# AIO.net
KiCad netlist of a schematic drawn in EAGLE
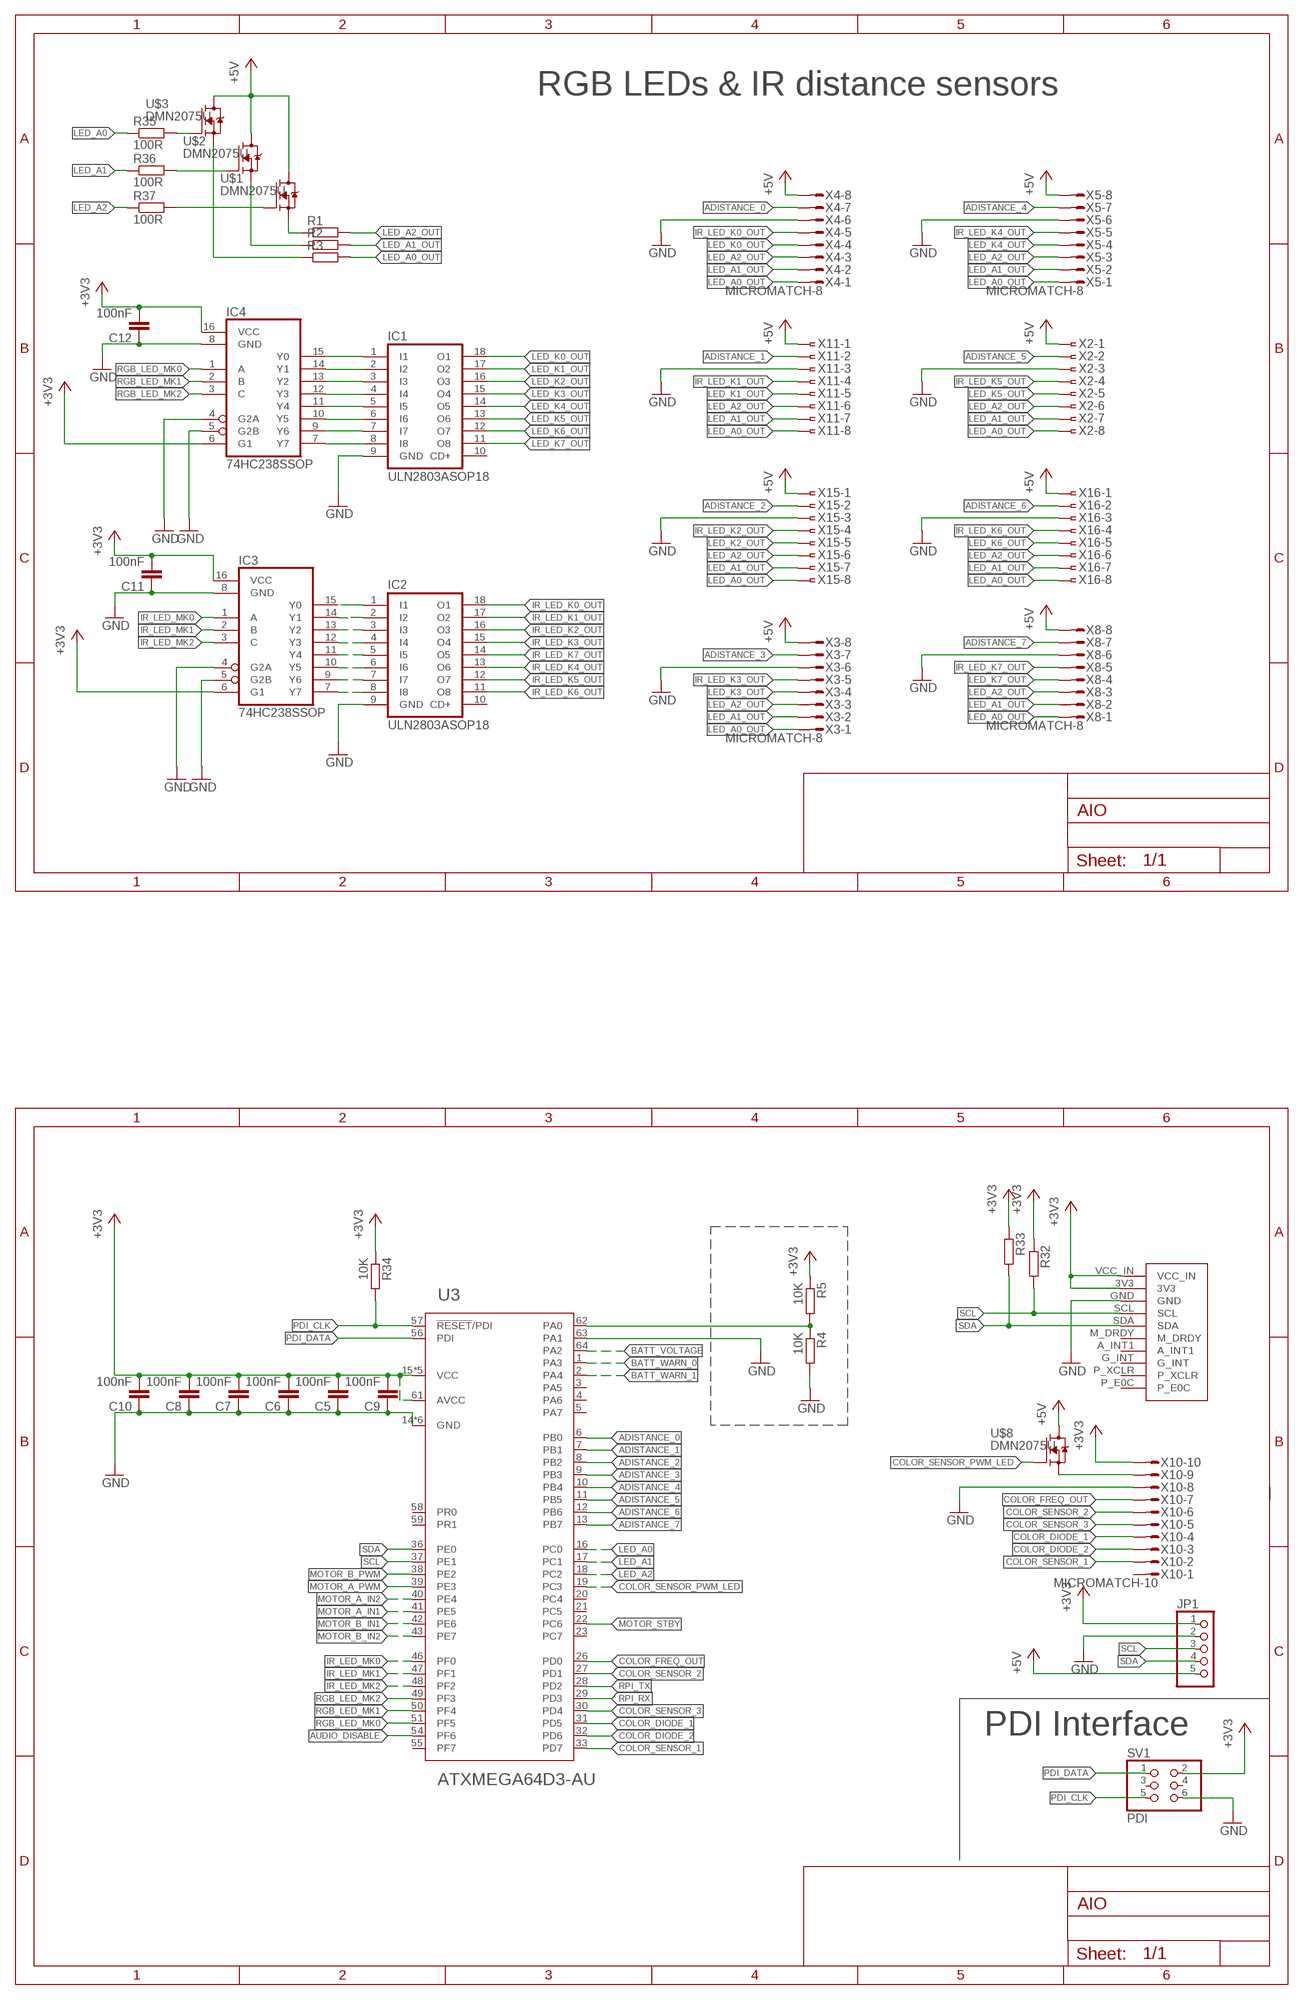
[diagram p0: schematic, sheet 1, part 1 of 2]
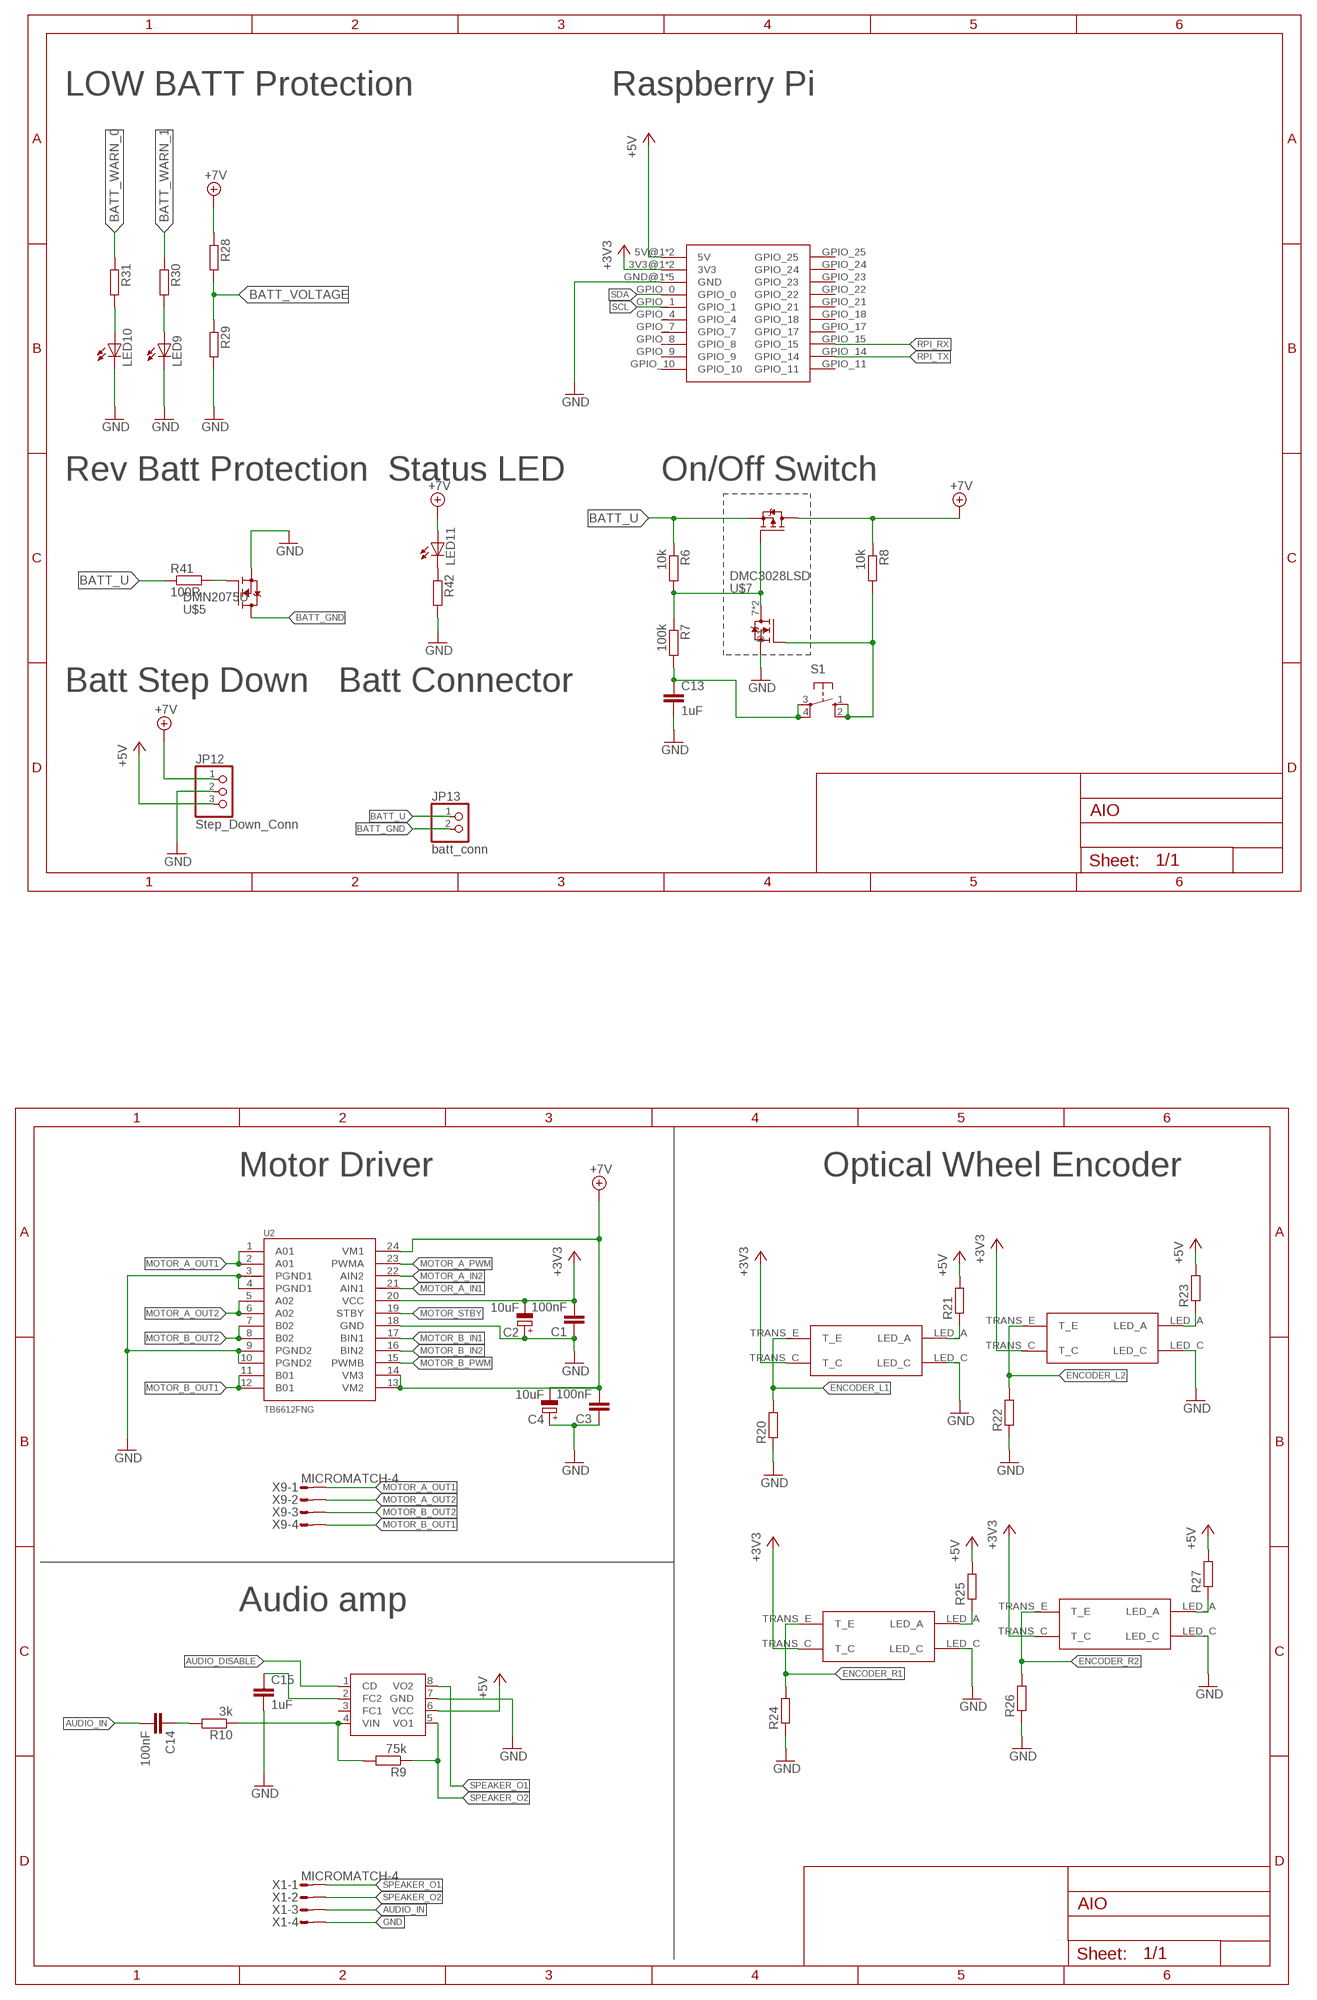
[diagram p1: schematic, sheet 1, part 2 of 2]

(export (version "E")
  (design (tool "Eeschema 10.0.6"))
  (components
    (comp (ref "C1")
      (value "100nF")
      (footprint "eagle-import:C0603")
      (libsource (lib "eagle-import") (part "C-EUC0603"))
    )
    (comp (ref "C2")
      (value "10uF")
      (footprint "eagle-import:SMC_D")
      (libsource (lib "eagle-import") (part "CPOL-EUSMCD"))
    )
    (comp (ref "C3")
      (value "100nF")
      (footprint "eagle-import:C0603")
      (libsource (lib "eagle-import") (part "C-EUC0603"))
    )
    (comp (ref "C4")
      (value "10uF")
      (footprint "eagle-import:SMC_D")
      (libsource (lib "eagle-import") (part "CPOL-EUSMCD"))
    )
    (comp (ref "C5")
      (value "100nF")
      (footprint "eagle-import:C0603")
      (libsource (lib "eagle-import") (part "C-EUC0603"))
    )
    (comp (ref "C6")
      (value "100nF")
      (footprint "eagle-import:C0603")
      (libsource (lib "eagle-import") (part "C-EUC0603"))
    )
    (comp (ref "C7")
      (value "100nF")
      (footprint "eagle-import:C0603")
      (libsource (lib "eagle-import") (part "C-EUC0603"))
    )
    (comp (ref "C8")
      (value "100nF")
      (footprint "eagle-import:C0603")
      (libsource (lib "eagle-import") (part "C-EUC0603"))
    )
    (comp (ref "C9")
      (value "100nF")
      (footprint "eagle-import:C0603")
      (libsource (lib "eagle-import") (part "C-EUC0603"))
    )
    (comp (ref "C10")
      (value "100nF")
      (footprint "eagle-import:C0603")
      (libsource (lib "eagle-import") (part "C-EUC0603"))
    )
    (comp (ref "C11")
      (value "100nF")
      (footprint "eagle-import:C0603")
      (libsource (lib "eagle-import") (part "C-EUC0603"))
    )
    (comp (ref "C12")
      (value "100nF")
      (footprint "eagle-import:C0603")
      (libsource (lib "eagle-import") (part "C-EUC0603"))
    )
    (comp (ref "C13")
      (value "1uF")
      (footprint "eagle-import:C0603")
      (libsource (lib "eagle-import") (part "C-EUC0603"))
    )
    (comp (ref "C14")
      (value "100nF")
      (footprint "eagle-import:C0603")
      (libsource (lib "eagle-import") (part "C-EUC0603"))
    )
    (comp (ref "C15")
      (value "1uF")
      (footprint "eagle-import:C0603")
      (libsource (lib "eagle-import") (part "C-EUC0603"))
    )
    (comp (ref "IC1")
      (value "ULN2803ASOP18")
      (footprint "eagle-import:SOP18")
      (libsource (lib "eagle-import") (part "ULN2803ASOP18"))
    )
    (comp (ref "IC2")
      (value "ULN2803ASOP18")
      (footprint "eagle-import:SOP18")
      (libsource (lib "eagle-import") (part "ULN2803ASOP18"))
    )
    (comp (ref "IC3")
      (value "74HC238SSOP")
      (footprint "eagle-import:SSOP16")
      (libsource (lib "eagle-import") (part "74HC238SSOP"))
    )
    (comp (ref "IC4")
      (value "74HC238SSOP")
      (footprint "eagle-import:SSOP16")
      (libsource (lib "eagle-import") (part "74HC238SSOP"))
    )
    (comp (ref "IC5")
      (value "TS34119SMD")
      (footprint "eagle-import:SO08")
      (libsource (lib "eagle-import") (part "TS34119SMD"))
    )
    (comp (ref "JP1")
      (value "PINHD-1X5")
      (footprint "eagle-import:1X05")
      (libsource (lib "eagle-import") (part "PINHD-1X5"))
    )
    (comp (ref "JP12")
      (value "Step_Down_Conn")
      (footprint "eagle-import:1X03")
      (libsource (lib "eagle-import") (part "PINHD-1X3"))
    )
    (comp (ref "JP13")
      (value "batt_conn")
      (footprint "eagle-import:1X02")
      (libsource (lib "eagle-import") (part "PINHD-1X2"))
    )
    (comp (ref "LED9")
      (value "LEDCHIPLED_0603")
      (footprint "eagle-import:CHIPLED_0603")
      (libsource (lib "eagle-import") (part "LEDCHIPLED_0603"))
    )
    (comp (ref "LED10")
      (value "LEDCHIPLED_0603")
      (footprint "eagle-import:CHIPLED_0603")
      (libsource (lib "eagle-import") (part "LEDCHIPLED_0603"))
    )
    (comp (ref "LED11")
      (value "LEDCHIPLED_0603")
      (footprint "eagle-import:CHIPLED_0603")
      (libsource (lib "eagle-import") (part "LEDCHIPLED_0603"))
    )
    (comp (ref "R1")
      (value "R-EU_R0603")
      (footprint "eagle-import:R0603")
      (libsource (lib "eagle-import") (part "R-EU_R0603"))
    )
    (comp (ref "R2")
      (value "R-EU_R0603")
      (footprint "eagle-import:R0603")
      (libsource (lib "eagle-import") (part "R-EU_R0603"))
    )
    (comp (ref "R3")
      (value "R-EU_R0603")
      (footprint "eagle-import:R0603")
      (libsource (lib "eagle-import") (part "R-EU_R0603"))
    )
    (comp (ref "R4")
      (value "10K")
      (footprint "eagle-import:R0603")
      (libsource (lib "eagle-import") (part "R-EU_R0603"))
    )
    (comp (ref "R5")
      (value "10K")
      (footprint "eagle-import:R0603")
      (libsource (lib "eagle-import") (part "R-EU_R0603"))
    )
    (comp (ref "R6")
      (value "10k")
      (footprint "eagle-import:R0603")
      (libsource (lib "eagle-import") (part "R-EU_R0603"))
    )
    (comp (ref "R7")
      (value "100k")
      (footprint "eagle-import:R0603")
      (libsource (lib "eagle-import") (part "R-EU_R0603"))
    )
    (comp (ref "R8")
      (value "10k")
      (footprint "eagle-import:R0603")
      (libsource (lib "eagle-import") (part "R-EU_R0603"))
    )
    (comp (ref "R9")
      (value "75k")
      (footprint "eagle-import:R0603")
      (libsource (lib "eagle-import") (part "R-EU_R0603"))
    )
    (comp (ref "R10")
      (value "3k")
      (footprint "eagle-import:R0603")
      (libsource (lib "eagle-import") (part "R-EU_R0603"))
    )
    (comp (ref "R20")
      (value "R-EU_R0603")
      (footprint "eagle-import:R0603")
      (libsource (lib "eagle-import") (part "R-EU_R0603"))
    )
    (comp (ref "R21")
      (value "R-EU_R0603")
      (footprint "eagle-import:R0603")
      (libsource (lib "eagle-import") (part "R-EU_R0603"))
    )
    (comp (ref "R22")
      (value "R-EU_R0603")
      (footprint "eagle-import:R0603")
      (libsource (lib "eagle-import") (part "R-EU_R0603"))
    )
    (comp (ref "R23")
      (value "R-EU_R0603")
      (footprint "eagle-import:R0603")
      (libsource (lib "eagle-import") (part "R-EU_R0603"))
    )
    (comp (ref "R24")
      (value "R-EU_R0603")
      (footprint "eagle-import:R0603")
      (libsource (lib "eagle-import") (part "R-EU_R0603"))
    )
    (comp (ref "R25")
      (value "R-EU_R0603")
      (footprint "eagle-import:R0603")
      (libsource (lib "eagle-import") (part "R-EU_R0603"))
    )
    (comp (ref "R26")
      (value "R-EU_R0603")
      (footprint "eagle-import:R0603")
      (libsource (lib "eagle-import") (part "R-EU_R0603"))
    )
    (comp (ref "R27")
      (value "R-EU_R0603")
      (footprint "eagle-import:R0603")
      (libsource (lib "eagle-import") (part "R-EU_R0603"))
    )
    (comp (ref "R28")
      (value "R-EU_R0603")
      (footprint "eagle-import:R0603")
      (libsource (lib "eagle-import") (part "R-EU_R0603"))
    )
    (comp (ref "R29")
      (value "R-EU_R0603")
      (footprint "eagle-import:R0603")
      (libsource (lib "eagle-import") (part "R-EU_R0603"))
    )
    (comp (ref "R30")
      (value "R-EU_R0603")
      (footprint "eagle-import:R0603")
      (libsource (lib "eagle-import") (part "R-EU_R0603"))
    )
    (comp (ref "R31")
      (value "R-EU_R0603")
      (footprint "eagle-import:R0603")
      (libsource (lib "eagle-import") (part "R-EU_R0603"))
    )
    (comp (ref "R32")
      (value "R-EU_R0603")
      (footprint "eagle-import:R0603")
      (libsource (lib "eagle-import") (part "R-EU_R0603"))
    )
    (comp (ref "R33")
      (value "R-EU_R0603")
      (footprint "eagle-import:R0603")
      (libsource (lib "eagle-import") (part "R-EU_R0603"))
    )
    (comp (ref "R34")
      (value "10K")
      (footprint "eagle-import:R0603")
      (libsource (lib "eagle-import") (part "R-EU_R0603"))
    )
    (comp (ref "R35")
      (value "100R")
      (footprint "eagle-import:R0603")
      (libsource (lib "eagle-import") (part "R-EU_R0603"))
    )
    (comp (ref "R36")
      (value "100R")
      (footprint "eagle-import:R0603")
      (libsource (lib "eagle-import") (part "R-EU_R0603"))
    )
    (comp (ref "R37")
      (value "100R")
      (footprint "eagle-import:R0603")
      (libsource (lib "eagle-import") (part "R-EU_R0603"))
    )
    (comp (ref "R41")
      (value "100R")
      (footprint "eagle-import:R0603")
      (libsource (lib "eagle-import") (part "R-EU_R0603"))
    )
    (comp (ref "R42")
      (value "R-EU_R0603")
      (footprint "eagle-import:R0603")
      (libsource (lib "eagle-import") (part "R-EU_R0603"))
    )
    (comp (ref "S1")
      (value "10-XX")
      (footprint "eagle-import:B3F-10XX")
      (fields (field (name "MPN") "B3F-1000"))
      (libsource (lib "eagle-import") (part "10-XX"))
    )
    (comp (ref "SV1")
      (value "PDI")
      (footprint "eagle-import:2X03")
      (libsource (lib "eagle-import") (part "PINHD-2X3"))
    )
    (comp (ref "U$1")
      (value "DMN2075U")
      (footprint "eagle-import:SOT95P240X112-3N")
      (libsource (lib "eagle-import") (part "DMN2075U"))
    )
    (comp (ref "U$2")
      (value "DMN2075U")
      (footprint "eagle-import:SOT95P240X112-3N")
      (libsource (lib "eagle-import") (part "DMN2075U"))
    )
    (comp (ref "U$3")
      (value "DMN2075U")
      (footprint "eagle-import:SOT95P240X112-3N")
      (libsource (lib "eagle-import") (part "DMN2075U"))
    )
    (comp (ref "U$5")
      (value "DMN2075U")
      (footprint "eagle-import:SOT95P240X112-3N")
      (libsource (lib "eagle-import") (part "DMN2075U"))
    )
    (comp (ref "U$7")
      (value "DMC3028LSD")
      (footprint "eagle-import:SO08")
      (libsource (lib "eagle-import") (part "DMC3028LSD"))
    )
    (comp (ref "U$8")
      (value "DMN2075U")
      (footprint "eagle-import:SOT95P240X112-3N")
      (libsource (lib "eagle-import") (part "DMN2075U"))
    )
    (comp (ref "U$21")
      (value "CNY70")
      (footprint "eagle-import:CNY70")
      (libsource (lib "eagle-import") (part "CNY70"))
    )
    (comp (ref "U$22")
      (value "CNY70")
      (footprint "eagle-import:CNY70")
      (libsource (lib "eagle-import") (part "CNY70"))
    )
    (comp (ref "U$23")
      (value "CNY70")
      (footprint "eagle-import:CNY70")
      (libsource (lib "eagle-import") (part "CNY70"))
    )
    (comp (ref "U$24")
      (value "CNY70")
      (footprint "eagle-import:CNY70")
      (libsource (lib "eagle-import") (part "CNY70"))
    )
    (comp (ref "U$25")
      (value "GY-81")
      (footprint "eagle-import:GY-81")
      (libsource (lib "eagle-import") (part "GY-81"))
    )
    (comp (ref "U$26")
      (value "RASPBERRY-PI")
      (footprint "eagle-import:RASPERRRY-PI")
      (libsource (lib "eagle-import") (part "RASPBERRY-PI"))
    )
    (comp (ref "U2")
      (value "TB6612FNG")
      (footprint "eagle-import:SSOP24")
      (libsource (lib "eagle-import") (part "TB6621FNG"))
    )
    (comp (ref "U3")
      (value "ATXMEGA64D3-AU")
      (footprint "eagle-import:TQFP-64A-64")
      (libsource (lib "eagle-import") (part "ATXMEGA64D3-AU"))
    )
    (comp (ref "X1")
      (value "MICROMATCH-4")
      (footprint "eagle-import:MICROMATCH-4")
      (fields (field (name "MPN") "7-215464-4"))
      (libsource (lib "eagle-import") (part "MICROMATCH-4"))
    )
    (comp (ref "X2")
      (value "FSIDE-8")
      (footprint "eagle-import:FSIDE-8")
      (libsource (lib "eagle-import") (part "FSIDE-8"))
    )
    (comp (ref "X3")
      (value "MICROMATCH-8")
      (footprint "eagle-import:MICROMATCH-8")
      (fields (field (name "MF") "FARNELL") (field (name "MPN") "7-215464-8"))
      (libsource (lib "eagle-import") (part "MICROMATCH-8"))
    )
    (comp (ref "X4")
      (value "MICROMATCH-8")
      (footprint "eagle-import:MICROMATCH-8")
      (fields (field (name "MF") "FARNELL") (field (name "MPN") "7-215464-8"))
      (libsource (lib "eagle-import") (part "MICROMATCH-8"))
    )
    (comp (ref "X5")
      (value "MICROMATCH-8")
      (footprint "eagle-import:MICROMATCH-8")
      (fields (field (name "MF") "FARNELL") (field (name "MPN") "7-215464-8"))
      (libsource (lib "eagle-import") (part "MICROMATCH-8"))
    )
    (comp (ref "X8")
      (value "MICROMATCH-8")
      (footprint "eagle-import:MICROMATCH-8")
      (fields (field (name "MF") "FARNELL") (field (name "MPN") "7-215464-8"))
      (libsource (lib "eagle-import") (part "MICROMATCH-8"))
    )
    (comp (ref "X9")
      (value "MICROMATCH-4")
      (footprint "eagle-import:MICROMATCH-4")
      (fields (field (name "MPN") "7-215464-4"))
      (libsource (lib "eagle-import") (part "MICROMATCH-4"))
    )
    (comp (ref "X10")
      (value "MICROMATCH-10")
      (footprint "eagle-import:MICROMATCH-10")
      (fields (field (name "MF") "FARNELL") (field (name "MPN") "8-215464-0"))
      (libsource (lib "eagle-import") (part "MICROMATCH-10"))
    )
    (comp (ref "X11")
      (value "FSIDE-8")
      (footprint "eagle-import:FSIDE-8")
      (libsource (lib "eagle-import") (part "FSIDE-8"))
    )
    (comp (ref "X15")
      (value "FSIDE-8")
      (footprint "eagle-import:FSIDE-8")
      (libsource (lib "eagle-import") (part "FSIDE-8"))
    )
    (comp (ref "X16")
      (value "FSIDE-8")
      (footprint "eagle-import:FSIDE-8")
      (libsource (lib "eagle-import") (part "FSIDE-8"))
    )
  )
  (nets
    (net (code "1") (name "+3V3") (class "Default")
      (node (ref "C1") (pin "2") (pinfunction "2_2") (pintype "passive"))
      (node (ref "C10") (pin "2") (pinfunction "2_2") (pintype "passive"))
      (node (ref "C11") (pin "2") (pinfunction "2_2") (pintype "passive"))
      (node (ref "C12") (pin "2") (pinfunction "2_2") (pintype "passive"))
      (node (ref "C2") (pin "-") (pinfunction "-_-") (pintype "passive"))
      (node (ref "C5") (pin "2") (pinfunction "2_2") (pintype "passive"))
      (node (ref "C6") (pin "2") (pinfunction "2_2") (pintype "passive"))
      (node (ref "C7") (pin "2") (pinfunction "2_2") (pintype "passive"))
      (node (ref "C8") (pin "2") (pinfunction "2_2") (pintype "passive"))
      (node (ref "C9") (pin "2") (pinfunction "2_2") (pintype "passive"))
      (node (ref "IC3") (pin "16") (pinfunction "VCC_16") (pintype "power_in"))
      (node (ref "IC3") (pin "6") (pinfunction "G1_6") (pintype "input"))
      (node (ref "IC4") (pin "16") (pinfunction "VCC_16") (pintype "power_in"))
      (node (ref "IC4") (pin "6") (pinfunction "G1_6") (pintype "input"))
      (node (ref "JP1") (pin "1") (pinfunction "1_1") (pintype "passive"))
      (node (ref "R32") (pin "1") (pinfunction "1_1") (pintype "passive"))
      (node (ref "R33") (pin "1") (pinfunction "1_1") (pintype "passive"))
      (node (ref "R34") (pin "1") (pinfunction "1_1") (pintype "passive"))
      (node (ref "R5") (pin "1") (pinfunction "1_1") (pintype "passive"))
      (node (ref "SV1") (pin "2") (pinfunction "2_2") (pintype "passive"))
      (node (ref "U$21") (pin "TRANS_C") (pinfunction "T_C_TRANS_C") (pintype "bidirectional"))
      (node (ref "U$22") (pin "TRANS_C") (pinfunction "T_C_TRANS_C") (pintype "bidirectional"))
      (node (ref "U$23") (pin "TRANS_C") (pinfunction "T_C_TRANS_C") (pintype "bidirectional"))
      (node (ref "U$24") (pin "TRANS_C") (pinfunction "T_C_TRANS_C") (pintype "bidirectional"))
      (node (ref "U$25") (pin "3V3") (pinfunction "3V3_3V3") (pintype "bidirectional"))
      (node (ref "U$25") (pin "VCC_IN") (pinfunction "VCC_IN_VCC_IN") (pintype "bidirectional"))
      (node (ref "U$26") (pin "3V3@1") (pinfunction "3V3_3V3@1") (pintype "power_in"))
      (node (ref "U$26") (pin "3V3@2") (pinfunction "3V3_3V3@2") (pintype "power_in"))
      (node (ref "U2") (pin "20") (pinfunction "VCC_20") (pintype "bidirectional"))
      (node (ref "U3") (pin "15") (pinfunction "VCC_15") (pintype "power_in"))
      (node (ref "U3") (pin "25") (pinfunction "VCC_25") (pintype "power_in"))
      (node (ref "U3") (pin "35") (pinfunction "VCC_35") (pintype "power_in"))
      (node (ref "U3") (pin "45") (pinfunction "VCC_45") (pintype "power_in"))
      (node (ref "U3") (pin "53") (pinfunction "VCC_53") (pintype "power_in"))
      (node (ref "U3") (pin "61") (pinfunction "AVCC_61") (pintype "power_in"))
      (node (ref "X10") (pin "10") (pinfunction "S_10") (pintype "passive"))
    )
    (net (code "2") (name "+5V") (class "Default")
      (node (ref "IC5") (pin "6") (pinfunction "VCC_6") (pintype "bidirectional"))
      (node (ref "JP1") (pin "5") (pinfunction "5_5") (pintype "passive"))
      (node (ref "JP12") (pin "3") (pinfunction "3_3") (pintype "passive"))
      (node (ref "R21") (pin "2") (pinfunction "2_2") (pintype "passive"))
      (node (ref "R23") (pin "2") (pinfunction "2_2") (pintype "passive"))
      (node (ref "R25") (pin "2") (pinfunction "2_2") (pintype "passive"))
      (node (ref "R27") (pin "2") (pinfunction "2_2") (pintype "passive"))
      (node (ref "U$1") (pin "D") (pinfunction "D_D") (pintype "passive"))
      (node (ref "U$2") (pin "D") (pinfunction "D_D") (pintype "passive"))
      (node (ref "U$26") (pin "5V@1") (pinfunction "5V_5V@1") (pintype "power_in"))
      (node (ref "U$26") (pin "5V@2") (pinfunction "5V_5V@2") (pintype "power_in"))
      (node (ref "U$3") (pin "D") (pinfunction "D_D") (pintype "passive"))
      (node (ref "U$8") (pin "D") (pinfunction "D_D") (pintype "passive"))
      (node (ref "X11") (pin "1") (pinfunction "1_1") (pintype "passive"))
      (node (ref "X15") (pin "1") (pinfunction "1_1") (pintype "passive"))
      (node (ref "X16") (pin "1") (pinfunction "1_1") (pintype "passive"))
      (node (ref "X2") (pin "1") (pinfunction "1_1") (pintype "passive"))
      (node (ref "X3") (pin "8") (pinfunction "S_8") (pintype "passive"))
      (node (ref "X4") (pin "8") (pinfunction "S_8") (pintype "passive"))
      (node (ref "X5") (pin "8") (pinfunction "S_8") (pintype "passive"))
      (node (ref "X8") (pin "8") (pinfunction "S_8") (pintype "passive"))
    )
    (net (code "3") (name "+7V") (class "Default")
      (node (ref "C3") (pin "2") (pinfunction "2_2") (pintype "passive"))
      (node (ref "C4") (pin "-") (pinfunction "-_-") (pintype "passive"))
      (node (ref "JP12") (pin "1") (pinfunction "1_1") (pintype "passive"))
      (node (ref "LED11") (pin "A") (pinfunction "A_A") (pintype "passive"))
      (node (ref "R28") (pin "1") (pinfunction "1_1") (pintype "passive"))
      (node (ref "R8") (pin "1") (pinfunction "1_1") (pintype "passive"))
      (node (ref "U$7") (pin "5") (pinfunction "D2_5") (pintype "passive"))
      (node (ref "U$7") (pin "6") (pinfunction "D2_6") (pintype "passive"))
      (node (ref "U2") (pin "13") (pinfunction "VM2_13") (pintype "bidirectional"))
      (node (ref "U2") (pin "14") (pinfunction "VM3_14") (pintype "bidirectional"))
      (node (ref "U2") (pin "24") (pinfunction "VM1_24") (pintype "bidirectional"))
    )
    (net (code "4") (name "ADISTANCE_0") (class "Default")
      (node (ref "U3") (pin "6") (pinfunction "PB0_6") (pintype "bidirectional"))
      (node (ref "X4") (pin "7") (pinfunction "S_7") (pintype "passive"))
    )
    (net (code "5") (name "ADISTANCE_1") (class "Default")
      (node (ref "U3") (pin "7") (pinfunction "PB1_7") (pintype "bidirectional"))
      (node (ref "X11") (pin "2") (pinfunction "1_2") (pintype "passive"))
    )
    (net (code "6") (name "ADISTANCE_2") (class "Default")
      (node (ref "U3") (pin "8") (pinfunction "PB2_8") (pintype "bidirectional"))
      (node (ref "X15") (pin "2") (pinfunction "1_2") (pintype "passive"))
    )
    (net (code "7") (name "ADISTANCE_3") (class "Default")
      (node (ref "U3") (pin "9") (pinfunction "PB3_9") (pintype "bidirectional"))
      (node (ref "X3") (pin "7") (pinfunction "S_7") (pintype "passive"))
    )
    (net (code "8") (name "ADISTANCE_4") (class "Default")
      (node (ref "U3") (pin "10") (pinfunction "PB4_10") (pintype "bidirectional"))
      (node (ref "X5") (pin "7") (pinfunction "S_7") (pintype "passive"))
    )
    (net (code "9") (name "ADISTANCE_5") (class "Default")
      (node (ref "U3") (pin "11") (pinfunction "PB5_11") (pintype "bidirectional"))
      (node (ref "X2") (pin "2") (pinfunction "1_2") (pintype "passive"))
    )
    (net (code "10") (name "ADISTANCE_6") (class "Default")
      (node (ref "U3") (pin "12") (pinfunction "PB6_12") (pintype "bidirectional"))
      (node (ref "X16") (pin "2") (pinfunction "1_2") (pintype "passive"))
    )
    (net (code "11") (name "ADISTANCE_7") (class "Default")
      (node (ref "U3") (pin "13") (pinfunction "PB7_13") (pintype "bidirectional"))
      (node (ref "X8") (pin "7") (pinfunction "S_7") (pintype "passive"))
    )
    (net (code "12") (name "AUDIO_DISABLE") (class "Default")
      (node (ref "IC5") (pin "1") (pinfunction "CD_1") (pintype "bidirectional"))
      (node (ref "U3") (pin "54") (pinfunction "PF6_54") (pintype "bidirectional"))
    )
    (net (code "13") (name "AUDIO_IN") (class "Default")
      (node (ref "C14") (pin "2") (pinfunction "2_2") (pintype "passive"))
      (node (ref "X1") (pin "3") (pinfunction "S_3") (pintype "passive"))
    )
    (net (code "14") (name "BATT_GND") (class "Default")
      (node (ref "JP13") (pin "2") (pinfunction "2_2") (pintype "passive"))
      (node (ref "U$5") (pin "D") (pinfunction "D_D") (pintype "passive"))
    )
    (net (code "15") (name "BATT_U") (class "Default")
      (node (ref "JP13") (pin "1") (pinfunction "1_1") (pintype "passive"))
      (node (ref "R41") (pin "1") (pinfunction "1_1") (pintype "passive"))
      (node (ref "R6") (pin "1") (pinfunction "1_1") (pintype "passive"))
      (node (ref "U$7") (pin "3") (pinfunction "S2_3") (pintype "passive"))
    )
    (net (code "16") (name "BATT_VOLTAGE") (class "Default")
      (node (ref "R28") (pin "2") (pinfunction "2_2") (pintype "passive"))
      (node (ref "R29") (pin "1") (pinfunction "1_1") (pintype "passive"))
      (node (ref "U3") (pin "64") (pinfunction "PA2_64") (pintype "bidirectional"))
    )
    (net (code "17") (name "BATT_WARN_0") (class "Default")
      (node (ref "R31") (pin "1") (pinfunction "1_1") (pintype "passive"))
      (node (ref "U3") (pin "1") (pinfunction "PA3_1") (pintype "bidirectional"))
    )
    (net (code "18") (name "BATT_WARN_1") (class "Default")
      (node (ref "R30") (pin "1") (pinfunction "1_1") (pintype "passive"))
      (node (ref "U3") (pin "2") (pinfunction "PA4_2") (pintype "bidirectional"))
    )
    (net (code "19") (name "COLOR_DIODE_1") (class "Default")
      (node (ref "U3") (pin "31") (pinfunction "PD5_31") (pintype "bidirectional"))
      (node (ref "X10") (pin "4") (pinfunction "S_4") (pintype "passive"))
    )
    (net (code "20") (name "COLOR_DIODE_2") (class "Default")
      (node (ref "U3") (pin "32") (pinfunction "PD6_32") (pintype "bidirectional"))
      (node (ref "X10") (pin "3") (pinfunction "S_3") (pintype "passive"))
    )
    (net (code "21") (name "COLOR_FREQ_OUT") (class "Default")
      (node (ref "U3") (pin "26") (pinfunction "PD0_26") (pintype "bidirectional"))
      (node (ref "X10") (pin "7") (pinfunction "S_7") (pintype "passive"))
    )
    (net (code "22") (name "COLOR_SENSOR_1") (class "Default")
      (node (ref "U3") (pin "33") (pinfunction "PD7_33") (pintype "bidirectional"))
      (node (ref "X10") (pin "2") (pinfunction "S_2") (pintype "passive"))
    )
    (net (code "23") (name "COLOR_SENSOR_2") (class "Default")
      (node (ref "U3") (pin "27") (pinfunction "PD1_27") (pintype "bidirectional"))
      (node (ref "X10") (pin "6") (pinfunction "S_6") (pintype "passive"))
    )
    (net (code "24") (name "COLOR_SENSOR_3") (class "Default")
      (node (ref "U3") (pin "30") (pinfunction "PD4_30") (pintype "bidirectional"))
      (node (ref "X10") (pin "5") (pinfunction "S_5") (pintype "passive"))
    )
    (net (code "25") (name "COLOR_SENSOR_PWM_LED") (class "Default")
      (node (ref "U$8") (pin "G") (pinfunction "G_G") (pintype "passive"))
      (node (ref "U3") (pin "19") (pinfunction "PC3_19") (pintype "bidirectional"))
    )
    (net (code "26") (name "ENCODER_L1") (class "Default")
      (node (ref "R20") (pin "2") (pinfunction "2_2") (pintype "passive"))
      (node (ref "U$21") (pin "TRANS_E") (pinfunction "T_E_TRANS_E") (pintype "bidirectional"))
    )
    (net (code "27") (name "ENCODER_L2") (class "Default")
      (node (ref "R22") (pin "2") (pinfunction "2_2") (pintype "passive"))
      (node (ref "U$22") (pin "TRANS_E") (pinfunction "T_E_TRANS_E") (pintype "bidirectional"))
    )
    (net (code "28") (name "ENCODER_R1") (class "Default")
      (node (ref "R24") (pin "2") (pinfunction "2_2") (pintype "passive"))
      (node (ref "U$23") (pin "TRANS_E") (pinfunction "T_E_TRANS_E") (pintype "bidirectional"))
    )
    (net (code "29") (name "ENCODER_R2") (class "Default")
      (node (ref "R26") (pin "2") (pinfunction "2_2") (pintype "passive"))
      (node (ref "U$24") (pin "TRANS_E") (pinfunction "T_E_TRANS_E") (pintype "bidirectional"))
    )
    (net (code "30") (name "GND") (class "Default")
      (node (ref "C1") (pin "1") (pinfunction "1_1") (pintype "passive"))
      (node (ref "C10") (pin "1") (pinfunction "1_1") (pintype "passive"))
      (node (ref "C11") (pin "1") (pinfunction "1_1") (pintype "passive"))
      (node (ref "C12") (pin "1") (pinfunction "1_1") (pintype "passive"))
      (node (ref "C13") (pin "2") (pinfunction "2_2") (pintype "passive"))
      (node (ref "C15") (pin "2") (pinfunction "2_2") (pintype "passive"))
      (node (ref "C2") (pin "+") (pinfunction "+_+") (pintype "passive"))
      (node (ref "C3") (pin "1") (pinfunction "1_1") (pintype "passive"))
      (node (ref "C4") (pin "+") (pinfunction "+_+") (pintype "passive"))
      (node (ref "C5") (pin "1") (pinfunction "1_1") (pintype "passive"))
      (node (ref "C6") (pin "1") (pinfunction "1_1") (pintype "passive"))
      (node (ref "C7") (pin "1") (pinfunction "1_1") (pintype "passive"))
      (node (ref "C8") (pin "1") (pinfunction "1_1") (pintype "passive"))
      (node (ref "C9") (pin "1") (pinfunction "1_1") (pintype "passive"))
      (node (ref "IC1") (pin "9") (pinfunction "GND_9") (pintype "power_in"))
      (node (ref "IC2") (pin "9") (pinfunction "GND_9") (pintype "power_in"))
      (node (ref "IC3") (pin "4") (pinfunction "G2A_4") (pintype "input"))
      (node (ref "IC3") (pin "5") (pinfunction "G2B_5") (pintype "input"))
      (node (ref "IC3") (pin "8") (pinfunction "GND_8") (pintype "power_in"))
      (node (ref "IC4") (pin "4") (pinfunction "G2A_4") (pintype "input"))
      (node (ref "IC4") (pin "5") (pinfunction "G2B_5") (pintype "input"))
      (node (ref "IC4") (pin "8") (pinfunction "GND_8") (pintype "power_in"))
      (node (ref "IC5") (pin "7") (pinfunction "GND_7") (pintype "bidirectional"))
      (node (ref "JP1") (pin "2") (pinfunction "2_2") (pintype "passive"))
      (node (ref "JP12") (pin "2") (pinfunction "2_2") (pintype "passive"))
      (node (ref "LED10") (pin "C") (pinfunction "C_C") (pintype "passive"))
      (node (ref "LED9") (pin "C") (pinfunction "C_C") (pintype "passive"))
      (node (ref "R20") (pin "1") (pinfunction "1_1") (pintype "passive"))
      (node (ref "R22") (pin "1") (pinfunction "1_1") (pintype "passive"))
      (node (ref "R24") (pin "1") (pinfunction "1_1") (pintype "passive"))
      (node (ref "R26") (pin "1") (pinfunction "1_1") (pintype "passive"))
      (node (ref "R29") (pin "2") (pinfunction "2_2") (pintype "passive"))
      (node (ref "R4") (pin "2") (pinfunction "2_2") (pintype "passive"))
      (node (ref "R42") (pin "2") (pinfunction "2_2") (pintype "passive"))
      (node (ref "SV1") (pin "6") (pinfunction "6_6") (pintype "passive"))
      (node (ref "U$21") (pin "LED_C") (pinfunction "LED_C_LED_C") (pintype "bidirectional"))
      (node (ref "U$22") (pin "LED_C") (pinfunction "LED_C_LED_C") (pintype "bidirectional"))
      (node (ref "U$23") (pin "LED_C") (pinfunction "LED_C_LED_C") (pintype "bidirectional"))
      (node (ref "U$24") (pin "LED_C") (pinfunction "LED_C_LED_C") (pintype "bidirectional"))
      (node (ref "U$25") (pin "GND") (pinfunction "GND_GND") (pintype "bidirectional"))
      (node (ref "U$26") (pin "GND@1") (pinfunction "GND_GND@1") (pintype "power_in"))
      (node (ref "U$26") (pin "GND@2") (pinfunction "GND_GND@2") (pintype "power_in"))
      (node (ref "U$26") (pin "GND@3") (pinfunction "GND_GND@3") (pintype "power_in"))
      (node (ref "U$26") (pin "GND@4") (pinfunction "GND_GND@4") (pintype "power_in"))
      (node (ref "U$26") (pin "GND@5") (pinfunction "GND_GND@5") (pintype "power_in"))
      (node (ref "U$5") (pin "S") (pinfunction "S_S") (pintype "passive"))
      (node (ref "U$7") (pin "1") (pinfunction "S1_1") (pintype "passive"))
      (node (ref "U2") (pin "10") (pinfunction "PGND2_10") (pintype "bidirectional"))
      (node (ref "U2") (pin "18") (pinfunction "GND_18") (pintype "bidirectional"))
      (node (ref "U2") (pin "3") (pinfunction "PGND1_3") (pintype "bidirectional"))
      (node (ref "U2") (pin "4") (pinfunction "PGND1_4") (pintype "bidirectional"))
      (node (ref "U2") (pin "9") (pinfunction "PGND2_9") (pintype "bidirectional"))
      (node (ref "U3") (pin "14") (pinfunction "GND_14") (pintype "power_in"))
      (node (ref "U3") (pin "24") (pinfunction "GND_24") (pintype "power_in"))
      (node (ref "U3") (pin "34") (pinfunction "GND_34") (pintype "power_in"))
      (node (ref "U3") (pin "44") (pinfunction "GND_44") (pintype "power_in"))
      (node (ref "U3") (pin "52") (pinfunction "GND_52") (pintype "power_in"))
      (node (ref "U3") (pin "60") (pinfunction "GND_60") (pintype "power_in"))
      (node (ref "U3") (pin "63") (pinfunction "PA1_63") (pintype "bidirectional"))
      (node (ref "X1") (pin "4") (pinfunction "S_4") (pintype "passive"))
      (node (ref "X10") (pin "8") (pinfunction "S_8") (pintype "passive"))
      (node (ref "X11") (pin "3") (pinfunction "1_3") (pintype "passive"))
      (node (ref "X15") (pin "3") (pinfunction "1_3") (pintype "passive"))
      (node (ref "X16") (pin "3") (pinfunction "1_3") (pintype "passive"))
      (node (ref "X2") (pin "3") (pinfunction "1_3") (pintype "passive"))
      (node (ref "X3") (pin "6") (pinfunction "S_6") (pintype "passive"))
      (node (ref "X4") (pin "6") (pinfunction "S_6") (pintype "passive"))
      (node (ref "X5") (pin "6") (pinfunction "S_6") (pintype "passive"))
      (node (ref "X8") (pin "6") (pinfunction "S_6") (pintype "passive"))
    )
    (net (code "31") (name "IR_LED_K0_OUT") (class "Default")
      (node (ref "IC2") (pin "18") (pinfunction "O1_18") (pintype "open_collector"))
      (node (ref "X4") (pin "5") (pinfunction "S_5") (pintype "passive"))
    )
    (net (code "32") (name "IR_LED_K1_OUT") (class "Default")
      (node (ref "IC2") (pin "17") (pinfunction "O2_17") (pintype "open_collector"))
      (node (ref "X11") (pin "4") (pinfunction "1_4") (pintype "passive"))
    )
    (net (code "33") (name "IR_LED_K2_OUT") (class "Default")
      (node (ref "IC2") (pin "16") (pinfunction "O3_16") (pintype "open_collector"))
      (node (ref "X15") (pin "4") (pinfunction "1_4") (pintype "passive"))
    )
    (net (code "34") (name "IR_LED_K3_OUT") (class "Default")
      (node (ref "IC2") (pin "15") (pinfunction "O4_15") (pintype "open_collector"))
      (node (ref "X3") (pin "5") (pinfunction "S_5") (pintype "passive"))
    )
    (net (code "35") (name "IR_LED_K4_OUT") (class "Default")
      (node (ref "IC2") (pin "13") (pinfunction "O6_13") (pintype "open_collector"))
      (node (ref "X5") (pin "5") (pinfunction "S_5") (pintype "passive"))
    )
    (net (code "36") (name "IR_LED_K5_OUT") (class "Default")
      (node (ref "IC2") (pin "12") (pinfunction "O7_12") (pintype "open_collector"))
      (node (ref "X2") (pin "4") (pinfunction "1_4") (pintype "passive"))
    )
    (net (code "37") (name "IR_LED_K6_OUT") (class "Default")
      (node (ref "IC2") (pin "11") (pinfunction "O8_11") (pintype "open_collector"))
      (node (ref "X16") (pin "4") (pinfunction "1_4") (pintype "passive"))
    )
    (net (code "38") (name "IR_LED_K7_OUT") (class "Default")
      (node (ref "IC2") (pin "14") (pinfunction "O5_14") (pintype "open_collector"))
      (node (ref "X8") (pin "5") (pinfunction "S_5") (pintype "passive"))
    )
    (net (code "39") (name "IR_LED_MK0") (class "Default")
      (node (ref "IC3") (pin "1") (pinfunction "A_1") (pintype "input"))
      (node (ref "U3") (pin "46") (pinfunction "PF0_46") (pintype "bidirectional"))
    )
    (net (code "40") (name "IR_LED_MK1") (class "Default")
      (node (ref "IC3") (pin "2") (pinfunction "B_2") (pintype "input"))
      (node (ref "U3") (pin "47") (pinfunction "PF1_47") (pintype "bidirectional"))
    )
    (net (code "41") (name "IR_LED_MK2") (class "Default")
      (node (ref "IC3") (pin "3") (pinfunction "C_3") (pintype "input"))
      (node (ref "U3") (pin "48") (pinfunction "PF2_48") (pintype "bidirectional"))
    )
    (net (code "42") (name "LED_A0") (class "Default")
      (node (ref "R35") (pin "1") (pinfunction "1_1") (pintype "passive"))
      (node (ref "U3") (pin "16") (pinfunction "PC0_16") (pintype "bidirectional"))
    )
    (net (code "43") (name "LED_A0_OUT") (class "Default")
      (node (ref "R3") (pin "2") (pinfunction "2_2") (pintype "passive"))
      (node (ref "X11") (pin "8") (pinfunction "1_8") (pintype "passive"))
      (node (ref "X15") (pin "8") (pinfunction "1_8") (pintype "passive"))
      (node (ref "X16") (pin "8") (pinfunction "1_8") (pintype "passive"))
      (node (ref "X2") (pin "8") (pinfunction "1_8") (pintype "passive"))
      (node (ref "X3") (pin "1") (pinfunction "S_1") (pintype "passive"))
      (node (ref "X4") (pin "1") (pinfunction "S_1") (pintype "passive"))
      (node (ref "X5") (pin "1") (pinfunction "S_1") (pintype "passive"))
      (node (ref "X8") (pin "1") (pinfunction "S_1") (pintype "passive"))
    )
    (net (code "44") (name "LED_A1") (class "Default")
      (node (ref "R36") (pin "1") (pinfunction "1_1") (pintype "passive"))
      (node (ref "U3") (pin "17") (pinfunction "PC1_17") (pintype "bidirectional"))
    )
    (net (code "45") (name "LED_A1_OUT") (class "Default")
      (node (ref "R2") (pin "2") (pinfunction "2_2") (pintype "passive"))
      (node (ref "X11") (pin "7") (pinfunction "1_7") (pintype "passive"))
      (node (ref "X15") (pin "7") (pinfunction "1_7") (pintype "passive"))
      (node (ref "X16") (pin "7") (pinfunction "1_7") (pintype "passive"))
      (node (ref "X2") (pin "7") (pinfunction "1_7") (pintype "passive"))
      (node (ref "X3") (pin "2") (pinfunction "S_2") (pintype "passive"))
      (node (ref "X4") (pin "2") (pinfunction "S_2") (pintype "passive"))
      (node (ref "X5") (pin "2") (pinfunction "S_2") (pintype "passive"))
      (node (ref "X8") (pin "2") (pinfunction "S_2") (pintype "passive"))
    )
    (net (code "46") (name "LED_A2") (class "Default")
      (node (ref "R37") (pin "1") (pinfunction "1_1") (pintype "passive"))
      (node (ref "U3") (pin "18") (pinfunction "PC2_18") (pintype "bidirectional"))
    )
    (net (code "47") (name "LED_A2_OUT") (class "Default")
      (node (ref "R1") (pin "2") (pinfunction "2_2") (pintype "passive"))
      (node (ref "X11") (pin "6") (pinfunction "1_6") (pintype "passive"))
      (node (ref "X15") (pin "6") (pinfunction "1_6") (pintype "passive"))
      (node (ref "X16") (pin "6") (pinfunction "1_6") (pintype "passive"))
      (node (ref "X2") (pin "6") (pinfunction "1_6") (pintype "passive"))
      (node (ref "X3") (pin "3") (pinfunction "S_3") (pintype "passive"))
      (node (ref "X4") (pin "3") (pinfunction "S_3") (pintype "passive"))
      (node (ref "X5") (pin "3") (pinfunction "S_3") (pintype "passive"))
      (node (ref "X8") (pin "3") (pinfunction "S_3") (pintype "passive"))
    )
    (net (code "48") (name "LED_K0_OUT") (class "Default")
      (node (ref "IC1") (pin "18") (pinfunction "O1_18") (pintype "open_collector"))
      (node (ref "X4") (pin "4") (pinfunction "S_4") (pintype "passive"))
    )
    (net (code "49") (name "LED_K1_OUT") (class "Default")
      (node (ref "IC1") (pin "17") (pinfunction "O2_17") (pintype "open_collector"))
      (node (ref "X11") (pin "5") (pinfunction "1_5") (pintype "passive"))
    )
    (net (code "50") (name "LED_K2_OUT") (class "Default")
      (node (ref "IC1") (pin "16") (pinfunction "O3_16") (pintype "open_collector"))
      (node (ref "X15") (pin "5") (pinfunction "1_5") (pintype "passive"))
    )
    (net (code "51") (name "LED_K3_OUT") (class "Default")
      (node (ref "IC1") (pin "15") (pinfunction "O4_15") (pintype "open_collector"))
      (node (ref "X3") (pin "4") (pinfunction "S_4") (pintype "passive"))
    )
    (net (code "52") (name "LED_K4_OUT") (class "Default")
      (node (ref "IC1") (pin "14") (pinfunction "O5_14") (pintype "open_collector"))
      (node (ref "X5") (pin "4") (pinfunction "S_4") (pintype "passive"))
    )
    (net (code "53") (name "LED_K5_OUT") (class "Default")
      (node (ref "IC1") (pin "13") (pinfunction "O6_13") (pintype "open_collector"))
      (node (ref "X2") (pin "5") (pinfunction "1_5") (pintype "passive"))
    )
    (net (code "54") (name "LED_K6_OUT") (class "Default")
      (node (ref "IC1") (pin "12") (pinfunction "O7_12") (pintype "open_collector"))
      (node (ref "X16") (pin "5") (pinfunction "1_5") (pintype "passive"))
    )
    (net (code "55") (name "LED_K7_OUT") (class "Default")
      (node (ref "IC1") (pin "11") (pinfunction "O8_11") (pintype "open_collector"))
      (node (ref "X8") (pin "4") (pinfunction "S_4") (pintype "passive"))
    )
    (net (code "56") (name "MOTOR_A_IN1") (class "Default")
      (node (ref "U2") (pin "21") (pinfunction "AIN1_21") (pintype "bidirectional"))
      (node (ref "U3") (pin "41") (pinfunction "PE5_41") (pintype "bidirectional"))
    )
    (net (code "57") (name "MOTOR_A_IN2") (class "Default")
      (node (ref "U2") (pin "22") (pinfunction "AIN2_22") (pintype "bidirectional"))
      (node (ref "U3") (pin "40") (pinfunction "PE4_40") (pintype "bidirectional"))
    )
    (net (code "58") (name "MOTOR_A_OUT1") (class "Default")
      (node (ref "U2") (pin "1") (pinfunction "A01_1") (pintype "bidirectional"))
      (node (ref "U2") (pin "2") (pinfunction "A01_2") (pintype "bidirectional"))
      (node (ref "X9") (pin "1") (pinfunction "S_1") (pintype "passive"))
    )
    (net (code "59") (name "MOTOR_A_OUT2") (class "Default")
      (node (ref "U2") (pin "5") (pinfunction "A02_5") (pintype "bidirectional"))
      (node (ref "U2") (pin "6") (pinfunction "A02_6") (pintype "bidirectional"))
      (node (ref "X9") (pin "2") (pinfunction "S_2") (pintype "passive"))
    )
    (net (code "60") (name "MOTOR_A_PWM") (class "Default")
      (node (ref "U2") (pin "23") (pinfunction "PWMA_23") (pintype "bidirectional"))
      (node (ref "U3") (pin "39") (pinfunction "PE3_39") (pintype "bidirectional"))
    )
    (net (code "61") (name "MOTOR_B_IN1") (class "Default")
      (node (ref "U2") (pin "17") (pinfunction "BIN1_17") (pintype "bidirectional"))
      (node (ref "U3") (pin "42") (pinfunction "PE6_42") (pintype "bidirectional"))
    )
    (net (code "62") (name "MOTOR_B_IN2") (class "Default")
      (node (ref "U2") (pin "16") (pinfunction "BIN2_16") (pintype "bidirectional"))
      (node (ref "U3") (pin "43") (pinfunction "PE7_43") (pintype "bidirectional"))
    )
    (net (code "63") (name "MOTOR_B_OUT1") (class "Default")
      (node (ref "U2") (pin "11") (pinfunction "B01_11") (pintype "bidirectional"))
      (node (ref "U2") (pin "12") (pinfunction "B01_12") (pintype "bidirectional"))
      (node (ref "X9") (pin "4") (pinfunction "S_4") (pintype "passive"))
    )
    (net (code "64") (name "MOTOR_B_OUT2") (class "Default")
      (node (ref "U2") (pin "7") (pinfunction "B02_7") (pintype "bidirectional"))
      (node (ref "U2") (pin "8") (pinfunction "B02_8") (pintype "bidirectional"))
      (node (ref "X9") (pin "3") (pinfunction "S_3") (pintype "passive"))
    )
    (net (code "65") (name "MOTOR_B_PWM") (class "Default")
      (node (ref "U2") (pin "15") (pinfunction "PWMB_15") (pintype "bidirectional"))
      (node (ref "U3") (pin "38") (pinfunction "PE2_38") (pintype "bidirectional"))
    )
    (net (code "66") (name "MOTOR_STBY") (class "Default")
      (node (ref "U2") (pin "19") (pinfunction "STBY_19") (pintype "bidirectional"))
      (node (ref "U3") (pin "22") (pinfunction "PC6_22") (pintype "bidirectional"))
    )
    (net (code "67") (name "Net-(C14-Pad1)") (class "Default")
      (node (ref "C14") (pin "1") (pinfunction "1_1") (pintype "passive"))
      (node (ref "R10") (pin "2") (pinfunction "2_2") (pintype "passive"))
    )
    (net (code "68") (name "Net-(IC1-I1)") (class "Default")
      (node (ref "IC1") (pin "1") (pinfunction "I1_1") (pintype "input"))
      (node (ref "IC4") (pin "15") (pinfunction "Y0_15") (pintype "output"))
    )
    (net (code "69") (name "Net-(IC1-I2)") (class "Default")
      (node (ref "IC1") (pin "2") (pinfunction "I2_2") (pintype "input"))
      (node (ref "IC4") (pin "14") (pinfunction "Y1_14") (pintype "output"))
    )
    (net (code "70") (name "Net-(IC1-I3)") (class "Default")
      (node (ref "IC1") (pin "3") (pinfunction "I3_3") (pintype "input"))
      (node (ref "IC4") (pin "13") (pinfunction "Y2_13") (pintype "output"))
    )
    (net (code "71") (name "Net-(IC1-I4)") (class "Default")
      (node (ref "IC1") (pin "4") (pinfunction "I4_4") (pintype "input"))
      (node (ref "IC4") (pin "12") (pinfunction "Y3_12") (pintype "output"))
    )
    (net (code "72") (name "Net-(IC1-I5)") (class "Default")
      (node (ref "IC1") (pin "5") (pinfunction "I5_5") (pintype "input"))
      (node (ref "IC4") (pin "11") (pinfunction "Y4_11") (pintype "output"))
    )
    (net (code "73") (name "Net-(IC1-I6)") (class "Default")
      (node (ref "IC1") (pin "6") (pinfunction "I6_6") (pintype "input"))
      (node (ref "IC4") (pin "10") (pinfunction "Y5_10") (pintype "output"))
    )
    (net (code "74") (name "Net-(IC1-I7)") (class "Default")
      (node (ref "IC1") (pin "7") (pinfunction "I7_7") (pintype "input"))
      (node (ref "IC4") (pin "9") (pinfunction "Y6_9") (pintype "output"))
    )
    (net (code "75") (name "Net-(IC1-I8)") (class "Default")
      (node (ref "IC1") (pin "8") (pinfunction "I8_8") (pintype "input"))
      (node (ref "IC4") (pin "7") (pinfunction "Y7_7") (pintype "output"))
    )
    (net (code "76") (name "Net-(IC2-I1)") (class "Default")
      (node (ref "IC2") (pin "1") (pinfunction "I1_1") (pintype "input"))
      (node (ref "IC3") (pin "15") (pinfunction "Y0_15") (pintype "output"))
    )
    (net (code "77") (name "Net-(IC2-I2)") (class "Default")
      (node (ref "IC2") (pin "2") (pinfunction "I2_2") (pintype "input"))
      (node (ref "IC3") (pin "14") (pinfunction "Y1_14") (pintype "output"))
    )
    (net (code "78") (name "Net-(IC2-I3)") (class "Default")
      (node (ref "IC2") (pin "3") (pinfunction "I3_3") (pintype "input"))
      (node (ref "IC3") (pin "13") (pinfunction "Y2_13") (pintype "output"))
    )
    (net (code "79") (name "Net-(IC2-I4)") (class "Default")
      (node (ref "IC2") (pin "4") (pinfunction "I4_4") (pintype "input"))
      (node (ref "IC3") (pin "12") (pinfunction "Y3_12") (pintype "output"))
    )
    (net (code "80") (name "Net-(IC2-I5)") (class "Default")
      (node (ref "IC2") (pin "5") (pinfunction "I5_5") (pintype "input"))
      (node (ref "IC3") (pin "11") (pinfunction "Y4_11") (pintype "output"))
    )
    (net (code "81") (name "Net-(IC2-I6)") (class "Default")
      (node (ref "IC2") (pin "6") (pinfunction "I6_6") (pintype "input"))
      (node (ref "IC3") (pin "10") (pinfunction "Y5_10") (pintype "output"))
    )
    (net (code "82") (name "Net-(IC2-I7)") (class "Default")
      (node (ref "IC2") (pin "7") (pinfunction "I7_7") (pintype "input"))
      (node (ref "IC3") (pin "9") (pinfunction "Y6_9") (pintype "output"))
    )
    (net (code "83") (name "Net-(IC2-I8)") (class "Default")
      (node (ref "IC2") (pin "8") (pinfunction "I8_8") (pintype "input"))
      (node (ref "IC3") (pin "7") (pinfunction "Y7_7") (pintype "output"))
    )
    (net (code "84") (name "Net-(IC5-FC2)") (class "Default")
      (node (ref "C15") (pin "1") (pinfunction "1_1") (pintype "passive"))
      (node (ref "IC5") (pin "2") (pinfunction "FC2_2") (pintype "bidirectional"))
    )
    (net (code "85") (name "Net-(IC5-VIN)") (class "Default")
      (node (ref "IC5") (pin "4") (pinfunction "VIN_4") (pintype "bidirectional"))
      (node (ref "R10") (pin "1") (pinfunction "1_1") (pintype "passive"))
      (node (ref "R9") (pin "2") (pinfunction "2_2") (pintype "passive"))
    )
    (net (code "86") (name "Net-(LED9-PadA)") (class "Default")
      (node (ref "LED9") (pin "A") (pinfunction "A_A") (pintype "passive"))
      (node (ref "R30") (pin "2") (pinfunction "2_2") (pintype "passive"))
    )
    (net (code "87") (name "Net-(LED10-PadA)") (class "Default")
      (node (ref "LED10") (pin "A") (pinfunction "A_A") (pintype "passive"))
      (node (ref "R31") (pin "2") (pinfunction "2_2") (pintype "passive"))
    )
    (net (code "88") (name "Net-(LED11-PadC)") (class "Default")
      (node (ref "LED11") (pin "C") (pinfunction "C_C") (pintype "passive"))
      (node (ref "R42") (pin "1") (pinfunction "1_1") (pintype "passive"))
    )
    (net (code "89") (name "Net-(R1-Pad1)") (class "Default")
      (node (ref "R1") (pin "1") (pinfunction "1_1") (pintype "passive"))
      (node (ref "U$1") (pin "S") (pinfunction "S_S") (pintype "passive"))
    )
    (net (code "90") (name "Net-(R2-Pad1)") (class "Default")
      (node (ref "R2") (pin "1") (pinfunction "1_1") (pintype "passive"))
      (node (ref "U$2") (pin "S") (pinfunction "S_S") (pintype "passive"))
    )
    (net (code "91") (name "Net-(R3-Pad1)") (class "Default")
      (node (ref "R3") (pin "1") (pinfunction "1_1") (pintype "passive"))
      (node (ref "U$3") (pin "S") (pinfunction "S_S") (pintype "passive"))
    )
    (net (code "92") (name "Net-(R21-Pad1)") (class "Default")
      (node (ref "R21") (pin "1") (pinfunction "1_1") (pintype "passive"))
      (node (ref "U$21") (pin "LED_A") (pinfunction "LED_A_LED_A") (pintype "bidirectional"))
    )
    (net (code "93") (name "Net-(R23-Pad1)") (class "Default")
      (node (ref "R23") (pin "1") (pinfunction "1_1") (pintype "passive"))
      (node (ref "U$22") (pin "LED_A") (pinfunction "LED_A_LED_A") (pintype "bidirectional"))
    )
    (net (code "94") (name "Net-(R25-Pad1)") (class "Default")
      (node (ref "R25") (pin "1") (pinfunction "1_1") (pintype "passive"))
      (node (ref "U$23") (pin "LED_A") (pinfunction "LED_A_LED_A") (pintype "bidirectional"))
    )
    (net (code "95") (name "Net-(R27-Pad1)") (class "Default")
      (node (ref "R27") (pin "1") (pinfunction "1_1") (pintype "passive"))
      (node (ref "U$24") (pin "LED_A") (pinfunction "LED_A_LED_A") (pintype "bidirectional"))
    )
    (net (code "96") (name "Net-(R35-Pad2)") (class "Default")
      (node (ref "R35") (pin "2") (pinfunction "2_2") (pintype "passive"))
      (node (ref "U$3") (pin "G") (pinfunction "G_G") (pintype "passive"))
    )
    (net (code "97") (name "Net-(R36-Pad2)") (class "Default")
      (node (ref "R36") (pin "2") (pinfunction "2_2") (pintype "passive"))
      (node (ref "U$2") (pin "G") (pinfunction "G_G") (pintype "passive"))
    )
    (net (code "98") (name "Net-(R37-Pad2)") (class "Default")
      (node (ref "R37") (pin "2") (pinfunction "2_2") (pintype "passive"))
      (node (ref "U$1") (pin "G") (pinfunction "G_G") (pintype "passive"))
    )
    (net (code "99") (name "Net-(R41-Pad2)") (class "Default")
      (node (ref "R41") (pin "2") (pinfunction "2_2") (pintype "passive"))
      (node (ref "U$5") (pin "G") (pinfunction "G_G") (pintype "passive"))
    )
    (net (code "100") (name "Net-(S1-P)") (class "Default")
      (node (ref "C13") (pin "1") (pinfunction "1_1") (pintype "passive"))
      (node (ref "R7") (pin "2") (pinfunction "2_2") (pintype "passive"))
      (node (ref "S1") (pin "3") (pinfunction "P_3") (pintype "passive"))
      (node (ref "S1") (pin "4") (pinfunction "P1_4") (pintype "passive"))
    )
    (net (code "101") (name "Net-(S1-S)") (class "Default")
      (node (ref "R8") (pin "2") (pinfunction "2_2") (pintype "passive"))
      (node (ref "S1") (pin "1") (pinfunction "S_1") (pintype "passive"))
      (node (ref "S1") (pin "2") (pinfunction "S1_2") (pintype "passive"))
      (node (ref "U$7") (pin "2") (pinfunction "G1_2") (pintype "passive"))
    )
    (net (code "102") (name "Net-(U$7-G2)") (class "Default")
      (node (ref "R6") (pin "2") (pinfunction "2_2") (pintype "passive"))
      (node (ref "R7") (pin "1") (pinfunction "1_1") (pintype "passive"))
      (node (ref "U$7") (pin "4") (pinfunction "G2_4") (pintype "passive"))
      (node (ref "U$7") (pin "7") (pinfunction "D1_7") (pintype "bidirectional"))
      (node (ref "U$7") (pin "8") (pinfunction "D1_8") (pintype "bidirectional"))
    )
    (net (code "103") (name "Net-(U3-PA0)") (class "Default")
      (node (ref "R4") (pin "1") (pinfunction "1_1") (pintype "passive"))
      (node (ref "R5") (pin "2") (pinfunction "2_2") (pintype "passive"))
      (node (ref "U3") (pin "62") (pinfunction "PA0_62") (pintype "bidirectional"))
    )
    (net (code "104") (name "Net-(X10J-S)") (class "Default")
      (node (ref "U$8") (pin "S") (pinfunction "S_S") (pintype "passive"))
      (node (ref "X10") (pin "9") (pinfunction "S_9") (pintype "passive"))
    )
    (net (code "105") (name "PDI_CLK") (class "Default")
      (node (ref "R34") (pin "2") (pinfunction "2_2") (pintype "passive"))
      (node (ref "SV1") (pin "5") (pinfunction "5_5") (pintype "passive"))
      (node (ref "U3") (pin "57") (pinfunction "~{RESET}/PDI_57") (pintype "bidirectional"))
    )
    (net (code "106") (name "PDI_DATA") (class "Default")
      (node (ref "SV1") (pin "1") (pinfunction "1_1") (pintype "passive"))
      (node (ref "U3") (pin "56") (pinfunction "PDI_56") (pintype "bidirectional"))
    )
    (net (code "107") (name "RGB_LED_MK0") (class "Default")
      (node (ref "IC4") (pin "1") (pinfunction "A_1") (pintype "input"))
      (node (ref "U3") (pin "51") (pinfunction "PF5_51") (pintype "bidirectional"))
    )
    (net (code "108") (name "RGB_LED_MK1") (class "Default")
      (node (ref "IC4") (pin "2") (pinfunction "B_2") (pintype "input"))
      (node (ref "U3") (pin "50") (pinfunction "PF4_50") (pintype "bidirectional"))
    )
    (net (code "109") (name "RGB_LED_MK2") (class "Default")
      (node (ref "IC4") (pin "3") (pinfunction "C_3") (pintype "input"))
      (node (ref "U3") (pin "49") (pinfunction "PF3_49") (pintype "bidirectional"))
    )
    (net (code "110") (name "RPI_RX") (class "Default")
      (node (ref "U$26") (pin "GPIO_15") (pinfunction "GPIO_15_GPIO_15") (pintype "bidirectional"))
      (node (ref "U3") (pin "29") (pinfunction "PD3_29") (pintype "bidirectional"))
    )
    (net (code "111") (name "RPI_TX") (class "Default")
      (node (ref "U$26") (pin "GPIO_14") (pinfunction "GPIO_14_GPIO_14") (pintype "bidirectional"))
      (node (ref "U3") (pin "28") (pinfunction "PD2_28") (pintype "bidirectional"))
    )
    (net (code "112") (name "SCL") (class "Default")
      (node (ref "JP1") (pin "3") (pinfunction "3_3") (pintype "passive"))
      (node (ref "R32") (pin "2") (pinfunction "2_2") (pintype "passive"))
      (node (ref "U$25") (pin "SCL") (pinfunction "SCL_SCL") (pintype "bidirectional"))
      (node (ref "U$26") (pin "GPIO_1") (pinfunction "GPIO_1_GPIO_1") (pintype "bidirectional"))
      (node (ref "U3") (pin "37") (pinfunction "PE1_37") (pintype "bidirectional"))
    )
    (net (code "113") (name "SDA") (class "Default")
      (node (ref "JP1") (pin "4") (pinfunction "4_4") (pintype "passive"))
      (node (ref "R33") (pin "2") (pinfunction "2_2") (pintype "passive"))
      (node (ref "U$25") (pin "SDA") (pinfunction "SDA_SDA") (pintype "bidirectional"))
      (node (ref "U$26") (pin "GPIO_0") (pinfunction "GPIO_0_GPIO_0") (pintype "bidirectional"))
      (node (ref "U3") (pin "36") (pinfunction "PE0_36") (pintype "bidirectional"))
    )
    (net (code "114") (name "SPEAKER_O1") (class "Default")
      (node (ref "IC5") (pin "8") (pinfunction "VO2_8") (pintype "bidirectional"))
      (node (ref "X1") (pin "1") (pinfunction "S_1") (pintype "passive"))
    )
    (net (code "115") (name "SPEAKER_O2") (class "Default")
      (node (ref "IC5") (pin "5") (pinfunction "VO1_5") (pintype "bidirectional"))
      (node (ref "R9") (pin "1") (pinfunction "1_1") (pintype "passive"))
      (node (ref "X1") (pin "2") (pinfunction "S_2") (pintype "passive"))
    )
    (net (code "116") (name "unconnected-(IC1-CD+-Pad10)") (class "Default")
      (node (ref "IC1") (pin "10") (pinfunction "CD+_10") (pintype "passive"))
    )
    (net (code "117") (name "unconnected-(IC2-CD+-Pad10)") (class "Default")
      (node (ref "IC2") (pin "10") (pinfunction "CD+_10") (pintype "passive"))
    )
    (net (code "118") (name "unconnected-(IC5-FC1-Pad3)") (class "Default")
      (node (ref "IC5") (pin "3") (pinfunction "FC1_3") (pintype "bidirectional"))
    )
    (net (code "119") (name "unconnected-(SV1-Pad3)") (class "Default")
      (node (ref "SV1") (pin "3") (pinfunction "3_3") (pintype "passive"))
    )
    (net (code "120") (name "unconnected-(SV1-Pad4)") (class "Default")
      (node (ref "SV1") (pin "4") (pinfunction "4_4") (pintype "passive"))
    )
    (net (code "121") (name "unconnected-(U$25-PadA_INT1)") (class "Default")
      (node (ref "U$25") (pin "A_INT1") (pinfunction "A_INT1_A_INT1") (pintype "bidirectional"))
    )
    (net (code "122") (name "unconnected-(U$25-PadG_INT)") (class "Default")
      (node (ref "U$25") (pin "G_INT") (pinfunction "G_INT_G_INT") (pintype "bidirectional"))
    )
    (net (code "123") (name "unconnected-(U$25-PadM_DRDY)") (class "Default")
      (node (ref "U$25") (pin "M_DRDY") (pinfunction "M_DRDY_M_DRDY") (pintype "bidirectional"))
    )
    (net (code "124") (name "unconnected-(U$25-PadP_E0C)") (class "Default")
      (node (ref "U$25") (pin "P_E0C") (pinfunction "P_E0C_P_E0C") (pintype "bidirectional"))
    )
    (net (code "125") (name "unconnected-(U$25-PadP_XCLR)") (class "Default")
      (node (ref "U$25") (pin "P_XCLR") (pinfunction "P_XCLR_P_XCLR") (pintype "bidirectional"))
    )
    (net (code "126") (name "unconnected-(U$26-PadGPIO_4)") (class "Default")
      (node (ref "U$26") (pin "GPIO_4") (pinfunction "GPIO_4_GPIO_4") (pintype "bidirectional"))
    )
    (net (code "127") (name "unconnected-(U$26-PadGPIO_7)") (class "Default")
      (node (ref "U$26") (pin "GPIO_7") (pinfunction "GPIO_7_GPIO_7") (pintype "bidirectional"))
    )
    (net (code "128") (name "unconnected-(U$26-PadGPIO_8)") (class "Default")
      (node (ref "U$26") (pin "GPIO_8") (pinfunction "GPIO_8_GPIO_8") (pintype "bidirectional"))
    )
    (net (code "129") (name "unconnected-(U$26-PadGPIO_9)") (class "Default")
      (node (ref "U$26") (pin "GPIO_9") (pinfunction "GPIO_9_GPIO_9") (pintype "bidirectional"))
    )
    (net (code "130") (name "unconnected-(U$26-PadGPIO_10)") (class "Default")
      (node (ref "U$26") (pin "GPIO_10") (pinfunction "GPIO_10_GPIO_10") (pintype "bidirectional"))
    )
    (net (code "131") (name "unconnected-(U$26-PadGPIO_11)") (class "Default")
      (node (ref "U$26") (pin "GPIO_11") (pinfunction "GPIO_11_GPIO_11") (pintype "bidirectional"))
    )
    (net (code "132") (name "unconnected-(U$26-PadGPIO_17)") (class "Default")
      (node (ref "U$26") (pin "GPIO_17") (pinfunction "GPIO_17_GPIO_17") (pintype "bidirectional"))
    )
    (net (code "133") (name "unconnected-(U$26-PadGPIO_18)") (class "Default")
      (node (ref "U$26") (pin "GPIO_18") (pinfunction "GPIO_18_GPIO_18") (pintype "bidirectional"))
    )
    (net (code "134") (name "unconnected-(U$26-PadGPIO_21)") (class "Default")
      (node (ref "U$26") (pin "GPIO_21") (pinfunction "GPIO_21_GPIO_21") (pintype "bidirectional"))
    )
    (net (code "135") (name "unconnected-(U$26-PadGPIO_22)") (class "Default")
      (node (ref "U$26") (pin "GPIO_22") (pinfunction "GPIO_22_GPIO_22") (pintype "bidirectional"))
    )
    (net (code "136") (name "unconnected-(U$26-PadGPIO_23)") (class "Default")
      (node (ref "U$26") (pin "GPIO_23") (pinfunction "GPIO_23_GPIO_23") (pintype "bidirectional"))
    )
    (net (code "137") (name "unconnected-(U$26-PadGPIO_24)") (class "Default")
      (node (ref "U$26") (pin "GPIO_24") (pinfunction "GPIO_24_GPIO_24") (pintype "bidirectional"))
    )
    (net (code "138") (name "unconnected-(U$26-PadGPIO_25)") (class "Default")
      (node (ref "U$26") (pin "GPIO_25") (pinfunction "GPIO_25_GPIO_25") (pintype "bidirectional"))
    )
    (net (code "139") (name "unconnected-(U3-PA5-Pad3)") (class "Default")
      (node (ref "U3") (pin "3") (pinfunction "PA5_3") (pintype "bidirectional"))
    )
    (net (code "140") (name "unconnected-(U3-PA6-Pad4)") (class "Default")
      (node (ref "U3") (pin "4") (pinfunction "PA6_4") (pintype "bidirectional"))
    )
    (net (code "141") (name "unconnected-(U3-PA7-Pad5)") (class "Default")
      (node (ref "U3") (pin "5") (pinfunction "PA7_5") (pintype "bidirectional"))
    )
    (net (code "142") (name "unconnected-(U3-PC4-Pad20)") (class "Default")
      (node (ref "U3") (pin "20") (pinfunction "PC4_20") (pintype "bidirectional"))
    )
    (net (code "143") (name "unconnected-(U3-PC5-Pad21)") (class "Default")
      (node (ref "U3") (pin "21") (pinfunction "PC5_21") (pintype "bidirectional"))
    )
    (net (code "144") (name "unconnected-(U3-PC7-Pad23)") (class "Default")
      (node (ref "U3") (pin "23") (pinfunction "PC7_23") (pintype "bidirectional"))
    )
    (net (code "145") (name "unconnected-(U3-PF7-Pad55)") (class "Default")
      (node (ref "U3") (pin "55") (pinfunction "PF7_55") (pintype "bidirectional"))
    )
    (net (code "146") (name "unconnected-(U3-PR0-Pad58)") (class "Default")
      (node (ref "U3") (pin "58") (pinfunction "PR0_58") (pintype "bidirectional"))
    )
    (net (code "147") (name "unconnected-(U3-PR1-Pad59)") (class "Default")
      (node (ref "U3") (pin "59") (pinfunction "PR1_59") (pintype "bidirectional"))
    )
    (net (code "148") (name "unconnected-(X10A-S-Pad1)") (class "Default")
      (node (ref "X10") (pin "1") (pinfunction "S_1") (pintype "passive"))
    )
  )
)
